# Sheet2.net
KiCad netlist of a schematic drawn in Altium Designer
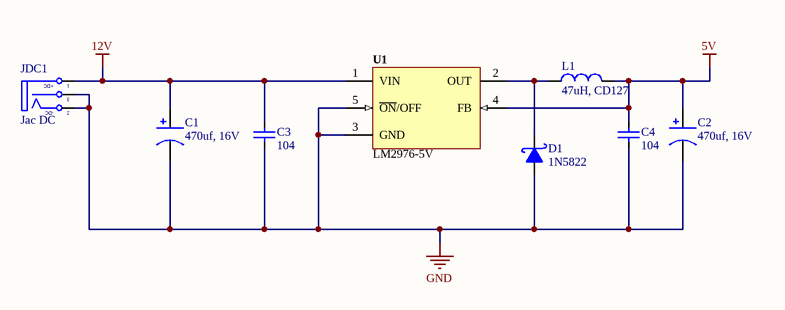
[diagram p0: Sheet2.SchDoc]

(export (version "E")
  (design (tool "Eeschema 10.0.6"))
  (components
    (comp (ref "C1")
      (value "470uf, 16V")
      (footprint "C8mm")
      (description "Polarized Capacitor (Axial)")
      (fields (field (name "PUBLISHER") "Altium Limited"))
      (libsource (lib "My Library") (part "Cap Pol"))
    )
    (comp (ref "C2")
      (value "470uf, 16V")
      (footprint "C8mm")
      (description "Polarized Capacitor (Axial)")
      (fields (field (name "PUBLISHER") "Altium Limited"))
      (libsource (lib "My Library") (part "Cap Pol"))
    )
    (comp (ref "C3")
      (value "104")
      (footprint "CAP_0805")
      (description "Capacitor")
      (fields (field (name "PUBLISHER") "Altium Limited"))
      (libsource (lib "My Library") (part "CapSMD"))
    )
    (comp (ref "C4")
      (value "104")
      (footprint "CAP_0805")
      (description "Capacitor")
      (fields (field (name "PUBLISHER") "Altium Limited"))
      (libsource (lib "My Library") (part "CapSMD"))
    )
    (comp (ref "D1")
      (value "1N5822")
      (footprint "SMA")
      (description "Schottky Rectifiers")
      (libsource (lib "My Library") (part "1N5822"))
    )
    (comp (ref "JDC1")
      (value "Jac DC")
      (footprint "DC-IN")
      (description "Jac DC input")
      (libsource (lib "My Library") (part "DCIN"))
    )
    (comp (ref "L1")
      (value "47uH, CD127")
      (footprint "L-SMD-M-12x10")
      (description "Inductor")
      (libsource (lib "My Library") (part "Inductor"))
    )
    (comp (ref "U1") (value "LM2976-5V") (footprint "TO-263") (libsource (lib "My Library") (part "LM2596")))
  )
  (nets
    (net (code "1") (name "5V") (class "Default")
      (node (ref "C2") (pin "1") (pinfunction "1_1") (pintype "passive"))
      (node (ref "C4") (pin "2") (pinfunction "2_2") (pintype "passive"))
      (node (ref "L1") (pin "2") (pinfunction "2_2") (pintype "passive"))
      (node (ref "U1") (pin "4") (pinfunction "FB_4") (pintype "input"))
    )
    (net (code "2") (name "12V") (class "Default")
      (node (ref "C1") (pin "1") (pinfunction "1_1") (pintype "passive"))
      (node (ref "C3") (pin "2") (pinfunction "2_2") (pintype "passive"))
      (node (ref "JDC1") (pin "1") (pinfunction "T_1") (pintype "passive"))
      (node (ref "U1") (pin "1") (pinfunction "VIN_1") (pintype "power_in"))
    )
    (net (code "3") (name "GND") (class "Default")
      (node (ref "C1") (pin "2") (pinfunction "2_2") (pintype "passive"))
      (node (ref "C2") (pin "2") (pinfunction "2_2") (pintype "passive"))
      (node (ref "C3") (pin "1") (pinfunction "1_1") (pintype "passive"))
      (node (ref "C4") (pin "1") (pinfunction "1_1") (pintype "passive"))
      (node (ref "D1") (pin "1") (pinfunction "A_1") (pintype "passive"))
      (node (ref "JDC1") (pin "2") (pinfunction "TN_2") (pintype "passive"))
      (node (ref "JDC1") (pin "3") (pinfunction "S_3") (pintype "power_in"))
      (node (ref "U1") (pin "3") (pinfunction "GND_3") (pintype "power_in"))
      (node (ref "U1") (pin "5") (pinfunction "~{ON}/OFF_5") (pintype "input"))
    )
    (net (code "4") (name "Net-(D1-K)") (class "Default")
      (node (ref "D1") (pin "2") (pinfunction "K_2") (pintype "passive"))
      (node (ref "L1") (pin "1") (pinfunction "1_1") (pintype "passive"))
      (node (ref "U1") (pin "2") (pinfunction "OUT_2") (pintype "power_in"))
    )
  )
)
